# misc.net
KiCad netlist of a schematic drawn in Altium Designer
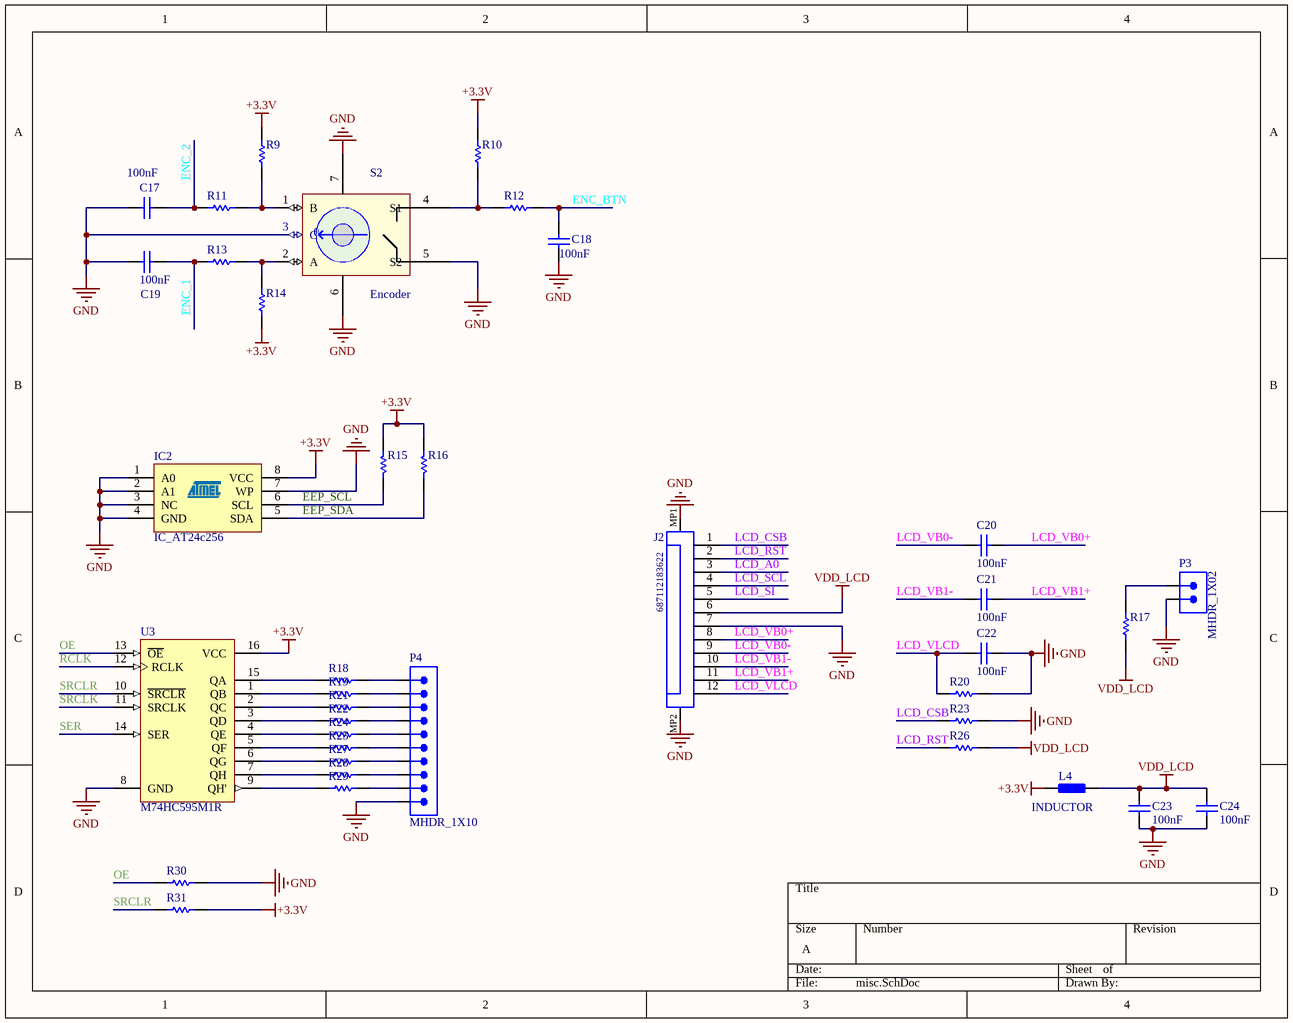
[diagram p0: misc.SchDoc]

(export (version "E")
  (design (tool "Eeschema 10.0.6"))
  (components
    (comp (ref "C17")
      (value "100nF")
      (footprint "CAPC3216M (1206)")
      (description "Bipolar Capacitor")
      (fields
        (field (name "VOLTAGE") "100V")
        (field (name "DESIGNER") "Eng. Saeid Jorablo")
        (field (name "PUBLISHER") "SJ Unlimited")
      )
      (libsource (lib "SJ Passive Components") (part "CAP_Bipolar"))
    )
    (comp (ref "C18")
      (value "100nF")
      (footprint "CAPC3216M (1206)")
      (description "Bipolar Capacitor")
      (fields
        (field (name "VOLTAGE") "100V")
        (field (name "DESIGNER") "Eng. Saeid Jorablo")
        (field (name "PUBLISHER") "SJ Unlimited")
      )
      (libsource (lib "SJ Passive Components") (part "CAP_Bipolar"))
    )
    (comp (ref "C19")
      (value "100nF")
      (footprint "CAPC3216M (1206)")
      (description "Bipolar Capacitor")
      (fields
        (field (name "VOLTAGE") "100V")
        (field (name "DESIGNER") "Eng. Saeid Jorablo")
        (field (name "PUBLISHER") "SJ Unlimited")
      )
      (libsource (lib "SJ Passive Components") (part "CAP_Bipolar"))
    )
    (comp (ref "C20")
      (value "100nF")
      (footprint "CAPC3216M (1206)")
      (description "Bipolar Capacitor")
      (fields
        (field (name "VOLTAGE") "100V")
        (field (name "DESIGNER") "Eng. Saeid Jorablo")
        (field (name "PUBLISHER") "SJ Unlimited")
      )
      (libsource (lib "SJ Passive Components") (part "CAP_Bipolar"))
    )
    (comp (ref "C21")
      (value "100nF")
      (footprint "CAPC3216M (1206)")
      (description "Bipolar Capacitor")
      (fields
        (field (name "VOLTAGE") "100V")
        (field (name "DESIGNER") "Eng. Saeid Jorablo")
        (field (name "PUBLISHER") "SJ Unlimited")
      )
      (libsource (lib "SJ Passive Components") (part "CAP_Bipolar"))
    )
    (comp (ref "C22")
      (value "100nF")
      (footprint "CAPC3216M (1206)")
      (description "Bipolar Capacitor")
      (fields
        (field (name "VOLTAGE") "100V")
        (field (name "DESIGNER") "Eng. Saeid Jorablo")
        (field (name "PUBLISHER") "SJ Unlimited")
      )
      (libsource (lib "SJ Passive Components") (part "CAP_Bipolar"))
    )
    (comp (ref "C23")
      (value "100nF")
      (footprint "CAPC3216M (1206)")
      (description "Bipolar Capacitor")
      (fields
        (field (name "VOLTAGE") "100V")
        (field (name "DESIGNER") "Eng. Saeid Jorablo")
        (field (name "PUBLISHER") "SJ Unlimited")
      )
      (libsource (lib "SJ Passive Components") (part "CAP_Bipolar"))
    )
    (comp (ref "C24")
      (value "100nF")
      (footprint "CAPC3216M (1206)")
      (description "Bipolar Capacitor")
      (fields
        (field (name "VOLTAGE") "100V")
        (field (name "DESIGNER") "Eng. Saeid Jorablo")
        (field (name "PUBLISHER") "SJ Unlimited")
      )
      (libsource (lib "SJ Passive Components") (part "CAP_Bipolar"))
    )
    (comp (ref "IC2")
      (value "IC_AT24c256")
      (footprint "CDIP8")
      (description "EEPROM Memory")
      (fields (field (name "DESIGNER") "Eng. Saeid Jorablo"))
      (libsource (lib "SJ Altium Library") (part "IC_AT24c256"))
    )
    (comp (ref "J2")
      (value "687112183622")
      (footprint "PCBComponent_1")
      (description "SMT ZIF Connectors Low Profile WR-FPC, Horizontal, Top Contact, pitch 0.6 mm, 12 pins")
      (fields (field (name "PUBLISHER") "Wurth Elektronik"))
      (libsource (lib "Altium_FPC_CONNECTORS (rev18c)") (part "687112183622"))
    )
    (comp (ref "L4")
      (value "INDUCTOR")
      (footprint "INDC4532")
      (description "Inductor")
      (fields (field (name "PUBLISHER") "SJ Unlimited") (field (name "DESIGNER") "Eng. Saeid Jorablo"))
      (libsource (lib "SJ Passive Components") (part "INDUCTOR"))
    )
    (comp (ref "P3")
      (value "MHDR_1X02")
      (footprint "MHDR1X02-254P")
      (description "Male Header 1X02")
      (libsource (lib "SJ Sockets & Connectors") (part "MHDR_1X02"))
    )
    (comp (ref "P4")
      (value "MHDR_1X10")
      (footprint "MHDR1X10-254P - E")
      (description "Male Header 1X10")
      (libsource (lib "SJ Sockets & Connectors") (part "MHDR_1X10"))
    )
    (comp (ref "R9")
      (value "1K")
      (footprint "RESC3216X60M (1206)")
      (description "Resistor")
      (fields
        (field (name "TOLERANCE") "5%")
        (field (name "POWER") "1/8 W")
        (field (name "DESIGNER") "Eng. Saeid Jorablo")
        (field (name "PUBLISHER") "SJ Unlimited")
      )
      (libsource (lib "SJ Passive Components") (part "RES"))
    )
    (comp (ref "R10")
      (value "1K")
      (footprint "RESC3216X60M (1206)")
      (description "Resistor")
      (fields
        (field (name "TOLERANCE") "5%")
        (field (name "POWER") "1/8 W")
        (field (name "DESIGNER") "Eng. Saeid Jorablo")
        (field (name "PUBLISHER") "SJ Unlimited")
      )
      (libsource (lib "SJ Passive Components") (part "RES"))
    )
    (comp (ref "R11")
      (value "1K")
      (footprint "RESC3216X60M (1206)")
      (description "Resistor")
      (fields
        (field (name "TOLERANCE") "5%")
        (field (name "POWER") "1/8 W")
        (field (name "DESIGNER") "Eng. Saeid Jorablo")
        (field (name "PUBLISHER") "SJ Unlimited")
      )
      (libsource (lib "SJ Passive Components") (part "RES"))
    )
    (comp (ref "R12")
      (value "1K")
      (footprint "RESC3216X60M (1206)")
      (description "Resistor")
      (fields
        (field (name "TOLERANCE") "5%")
        (field (name "POWER") "1/8 W")
        (field (name "DESIGNER") "Eng. Saeid Jorablo")
        (field (name "PUBLISHER") "SJ Unlimited")
      )
      (libsource (lib "SJ Passive Components") (part "RES"))
    )
    (comp (ref "R13")
      (value "1K")
      (footprint "RESC3216X60M (1206)")
      (description "Resistor")
      (fields
        (field (name "TOLERANCE") "5%")
        (field (name "POWER") "1/8 W")
        (field (name "DESIGNER") "Eng. Saeid Jorablo")
        (field (name "PUBLISHER") "SJ Unlimited")
      )
      (libsource (lib "SJ Passive Components") (part "RES"))
    )
    (comp (ref "R14")
      (value "1K")
      (footprint "RESC3216X60M (1206)")
      (description "Resistor")
      (fields
        (field (name "TOLERANCE") "5%")
        (field (name "POWER") "1/8 W")
        (field (name "DESIGNER") "Eng. Saeid Jorablo")
        (field (name "PUBLISHER") "SJ Unlimited")
      )
      (libsource (lib "SJ Passive Components") (part "RES"))
    )
    (comp (ref "R15")
      (value "1K")
      (footprint "RESC3216X60M (1206)")
      (description "Resistor")
      (fields
        (field (name "TOLERANCE") "5%")
        (field (name "POWER") "1/8 W")
        (field (name "DESIGNER") "Eng. Saeid Jorablo")
        (field (name "PUBLISHER") "SJ Unlimited")
      )
      (libsource (lib "SJ Passive Components") (part "RES"))
    )
    (comp (ref "R16")
      (value "1K")
      (footprint "RESC3216X60M (1206)")
      (description "Resistor")
      (fields
        (field (name "TOLERANCE") "5%")
        (field (name "POWER") "1/8 W")
        (field (name "DESIGNER") "Eng. Saeid Jorablo")
        (field (name "PUBLISHER") "SJ Unlimited")
      )
      (libsource (lib "SJ Passive Components") (part "RES"))
    )
    (comp (ref "R17")
      (value "1K")
      (footprint "RESC3216X60M (1206)")
      (description "Resistor")
      (fields
        (field (name "TOLERANCE") "5%")
        (field (name "POWER") "1/8 W")
        (field (name "DESIGNER") "Eng. Saeid Jorablo")
        (field (name "PUBLISHER") "SJ Unlimited")
      )
      (libsource (lib "SJ Passive Components") (part "RES"))
    )
    (comp (ref "R18")
      (value "1K")
      (footprint "RESC3216X60M (1206)")
      (description "Resistor")
      (fields
        (field (name "TOLERANCE") "5%")
        (field (name "POWER") "1/8 W")
        (field (name "DESIGNER") "Eng. Saeid Jorablo")
        (field (name "PUBLISHER") "SJ Unlimited")
      )
      (libsource (lib "SJ Passive Components") (part "RES"))
    )
    (comp (ref "R19")
      (value "1K")
      (footprint "RESC3216X60M (1206)")
      (description "Resistor")
      (fields
        (field (name "TOLERANCE") "5%")
        (field (name "POWER") "1/8 W")
        (field (name "DESIGNER") "Eng. Saeid Jorablo")
        (field (name "PUBLISHER") "SJ Unlimited")
      )
      (libsource (lib "SJ Passive Components") (part "RES"))
    )
    (comp (ref "R20")
      (value "1K")
      (footprint "RESC3216X60M (1206)")
      (description "Resistor")
      (fields
        (field (name "TOLERANCE") "5%")
        (field (name "POWER") "1/8 W")
        (field (name "DESIGNER") "Eng. Saeid Jorablo")
        (field (name "PUBLISHER") "SJ Unlimited")
      )
      (libsource (lib "SJ Passive Components") (part "RES"))
    )
    (comp (ref "R21")
      (value "1K")
      (footprint "RESC3216X60M (1206)")
      (description "Resistor")
      (fields
        (field (name "TOLERANCE") "5%")
        (field (name "POWER") "1/8 W")
        (field (name "DESIGNER") "Eng. Saeid Jorablo")
        (field (name "PUBLISHER") "SJ Unlimited")
      )
      (libsource (lib "SJ Passive Components") (part "RES"))
    )
    (comp (ref "R22")
      (value "1K")
      (footprint "RESC3216X60M (1206)")
      (description "Resistor")
      (fields
        (field (name "TOLERANCE") "5%")
        (field (name "POWER") "1/8 W")
        (field (name "DESIGNER") "Eng. Saeid Jorablo")
        (field (name "PUBLISHER") "SJ Unlimited")
      )
      (libsource (lib "SJ Passive Components") (part "RES"))
    )
    (comp (ref "R23")
      (value "1K")
      (footprint "RESC3216X60M (1206)")
      (description "Resistor")
      (fields
        (field (name "TOLERANCE") "5%")
        (field (name "POWER") "1/8 W")
        (field (name "DESIGNER") "Eng. Saeid Jorablo")
        (field (name "PUBLISHER") "SJ Unlimited")
      )
      (libsource (lib "SJ Passive Components") (part "RES"))
    )
    (comp (ref "R24")
      (value "1K")
      (footprint "RESC3216X60M (1206)")
      (description "Resistor")
      (fields
        (field (name "TOLERANCE") "5%")
        (field (name "POWER") "1/8 W")
        (field (name "DESIGNER") "Eng. Saeid Jorablo")
        (field (name "PUBLISHER") "SJ Unlimited")
      )
      (libsource (lib "SJ Passive Components") (part "RES"))
    )
    (comp (ref "R25")
      (value "1K")
      (footprint "RESC3216X60M (1206)")
      (description "Resistor")
      (fields
        (field (name "TOLERANCE") "5%")
        (field (name "POWER") "1/8 W")
        (field (name "DESIGNER") "Eng. Saeid Jorablo")
        (field (name "PUBLISHER") "SJ Unlimited")
      )
      (libsource (lib "SJ Passive Components") (part "RES"))
    )
    (comp (ref "R26")
      (value "1K")
      (footprint "RESC3216X60M (1206)")
      (description "Resistor")
      (fields
        (field (name "TOLERANCE") "5%")
        (field (name "POWER") "1/8 W")
        (field (name "DESIGNER") "Eng. Saeid Jorablo")
        (field (name "PUBLISHER") "SJ Unlimited")
      )
      (libsource (lib "SJ Passive Components") (part "RES"))
    )
    (comp (ref "R27")
      (value "1K")
      (footprint "RESC3216X60M (1206)")
      (description "Resistor")
      (fields
        (field (name "TOLERANCE") "5%")
        (field (name "POWER") "1/8 W")
        (field (name "DESIGNER") "Eng. Saeid Jorablo")
        (field (name "PUBLISHER") "SJ Unlimited")
      )
      (libsource (lib "SJ Passive Components") (part "RES"))
    )
    (comp (ref "R28")
      (value "1K")
      (footprint "RESC3216X60M (1206)")
      (description "Resistor")
      (fields
        (field (name "TOLERANCE") "5%")
        (field (name "POWER") "1/8 W")
        (field (name "DESIGNER") "Eng. Saeid Jorablo")
        (field (name "PUBLISHER") "SJ Unlimited")
      )
      (libsource (lib "SJ Passive Components") (part "RES"))
    )
    (comp (ref "R29")
      (value "1K")
      (footprint "RESC3216X60M (1206)")
      (description "Resistor")
      (fields
        (field (name "TOLERANCE") "5%")
        (field (name "POWER") "1/8 W")
        (field (name "DESIGNER") "Eng. Saeid Jorablo")
        (field (name "PUBLISHER") "SJ Unlimited")
      )
      (libsource (lib "SJ Passive Components") (part "RES"))
    )
    (comp (ref "R30")
      (value "1K")
      (footprint "RESC3216X60M (1206)")
      (description "Resistor")
      (fields
        (field (name "TOLERANCE") "5%")
        (field (name "POWER") "1/8 W")
        (field (name "DESIGNER") "Eng. Saeid Jorablo")
        (field (name "PUBLISHER") "SJ Unlimited")
      )
      (libsource (lib "SJ Passive Components") (part "RES"))
    )
    (comp (ref "R31")
      (value "1K")
      (footprint "RESC3216X60M (1206)")
      (description "Resistor")
      (fields
        (field (name "TOLERANCE") "5%")
        (field (name "POWER") "1/8 W")
        (field (name "DESIGNER") "Eng. Saeid Jorablo")
        (field (name "PUBLISHER") "SJ Unlimited")
      )
      (libsource (lib "SJ Passive Components") (part "RES"))
    )
    (comp (ref "S2") (value "Encoder") (footprint "Encoder") (libsource (lib "stm8") (part "Encoder")))
    (comp (ref "U3")
      (value "M74HC595M1R")
      (footprint "SO16_L")
      (description "8 Bit Shift Register with Output Latches (3 STATE)")
      (fields (field (name "PUBLISHER") "Altium Limited"))
      (libsource (lib "ST Logic Register") (part "M74HC595M1R"))
    )
  )
  (nets
    (net (code "1") (name "+3.3V") (class "Default")
      (node (ref "IC2") (pin "8") (pinfunction "VCC_8") (pintype "power_in"))
      (node (ref "L4") (pin "1") (pinfunction "1_1") (pintype "passive"))
      (node (ref "R10") (pin "2") (pinfunction "2_2") (pintype "passive"))
      (node (ref "R14") (pin "1") (pinfunction "1_1") (pintype "passive"))
      (node (ref "R15") (pin "1") (pinfunction "1_1") (pintype "passive"))
      (node (ref "R16") (pin "1") (pinfunction "1_1") (pintype "passive"))
      (node (ref "R31") (pin "1") (pinfunction "1_1") (pintype "passive"))
      (node (ref "R9") (pin "2") (pinfunction "2_2") (pintype "passive"))
      (node (ref "U3") (pin "16") (pinfunction "VCC_16") (pintype "power_in"))
    )
    (net (code "2") (name "/EEP_SCL") (class "Default")
      (node (ref "IC2") (pin "6") (pinfunction "SCL_6") (pintype "passive"))
      (node (ref "R15") (pin "2") (pinfunction "2_2") (pintype "passive"))
    )
    (net (code "3") (name "/EEP_SDA") (class "Default")
      (node (ref "IC2") (pin "5") (pinfunction "SDA_5") (pintype "passive"))
      (node (ref "R16") (pin "2") (pinfunction "2_2") (pintype "passive"))
    )
    (net (code "4") (name "/ENC_1") (class "Default")
      (node (ref "C19") (pin "2") (pinfunction "-_2") (pintype "passive"))
      (node (ref "R13") (pin "2") (pinfunction "2_2") (pintype "passive"))
    )
    (net (code "5") (name "/ENC_2") (class "Default")
      (node (ref "C17") (pin "2") (pinfunction "-_2") (pintype "passive"))
      (node (ref "R11") (pin "2") (pinfunction "2_2") (pintype "passive"))
    )
    (net (code "6") (name "/ENC_BTN") (class "Default")
      (node (ref "C18") (pin "1") (pinfunction "+_1") (pintype "passive"))
      (node (ref "R12") (pin "1") (pinfunction "1_1") (pintype "passive"))
    )
    (net (code "7") (name "/LCD_A0") (class "Default")
      (node (ref "J2") (pin "3") (pinfunction "3_3") (pintype "passive"))
    )
    (net (code "8") (name "/LCD_CSB") (class "Default")
      (node (ref "J2") (pin "1") (pinfunction "1_1") (pintype "passive"))
      (node (ref "R23") (pin "2") (pinfunction "2_2") (pintype "passive"))
    )
    (net (code "9") (name "/LCD_RST") (class "Default")
      (node (ref "J2") (pin "2") (pinfunction "2_2") (pintype "passive"))
      (node (ref "R26") (pin "2") (pinfunction "2_2") (pintype "passive"))
    )
    (net (code "10") (name "/LCD_SCL") (class "Default")
      (node (ref "J2") (pin "4") (pinfunction "4_4") (pintype "passive"))
    )
    (net (code "11") (name "/LCD_SI") (class "Default")
      (node (ref "J2") (pin "5") (pinfunction "5_5") (pintype "passive"))
    )
    (net (code "12") (name "/LCD_VB0+") (class "Default")
      (node (ref "C20") (pin "1") (pinfunction "+_1") (pintype "passive"))
      (node (ref "J2") (pin "8") (pinfunction "8_8") (pintype "passive"))
    )
    (net (code "13") (name "/LCD_VB0-") (class "Default")
      (node (ref "C20") (pin "2") (pinfunction "-_2") (pintype "passive"))
      (node (ref "J2") (pin "9") (pinfunction "9_9") (pintype "passive"))
    )
    (net (code "14") (name "/LCD_VB1+") (class "Default")
      (node (ref "C21") (pin "1") (pinfunction "+_1") (pintype "passive"))
      (node (ref "J2") (pin "11") (pinfunction "11_11") (pintype "passive"))
    )
    (net (code "15") (name "/LCD_VB1-") (class "Default")
      (node (ref "C21") (pin "2") (pinfunction "-_2") (pintype "passive"))
      (node (ref "J2") (pin "10") (pinfunction "10_10") (pintype "passive"))
    )
    (net (code "16") (name "/LCD_VLCD") (class "Default")
      (node (ref "C22") (pin "1") (pinfunction "+_1") (pintype "passive"))
      (node (ref "J2") (pin "12") (pinfunction "12_12") (pintype "passive"))
      (node (ref "R20") (pin "2") (pinfunction "2_2") (pintype "passive"))
    )
    (net (code "17") (name "/OE") (class "Default")
      (node (ref "R30") (pin "2") (pinfunction "2_2") (pintype "passive"))
      (node (ref "U3") (pin "13") (pinfunction "~{OE}_13") (pintype "input"))
    )
    (net (code "18") (name "/RCLK") (class "Default")
      (node (ref "U3") (pin "12") (pinfunction "RCLK_12") (pintype "input"))
    )
    (net (code "19") (name "/SER") (class "Default")
      (node (ref "U3") (pin "14") (pinfunction "SER_14") (pintype "input"))
    )
    (net (code "20") (name "/SRCLK") (class "Default")
      (node (ref "U3") (pin "11") (pinfunction "SRCLK_11") (pintype "input"))
    )
    (net (code "21") (name "/SRCLR") (class "Default")
      (node (ref "R31") (pin "2") (pinfunction "2_2") (pintype "passive"))
      (node (ref "U3") (pin "10") (pinfunction "~{SRCLR}_10") (pintype "input"))
    )
    (net (code "22") (name "GND") (class "Default")
      (node (ref "C17") (pin "1") (pinfunction "+_1") (pintype "passive"))
      (node (ref "C18") (pin "2") (pinfunction "-_2") (pintype "passive"))
      (node (ref "C19") (pin "1") (pinfunction "+_1") (pintype "passive"))
      (node (ref "C22") (pin "2") (pinfunction "-_2") (pintype "passive"))
      (node (ref "C23") (pin "2") (pinfunction "-_2") (pintype "passive"))
      (node (ref "C24") (pin "2") (pinfunction "-_2") (pintype "passive"))
      (node (ref "IC2") (pin "1") (pinfunction "A0_1") (pintype "passive"))
      (node (ref "IC2") (pin "2") (pinfunction "A1_2") (pintype "passive"))
      (node (ref "IC2") (pin "3") (pinfunction "NC_3") (pintype "passive"))
      (node (ref "IC2") (pin "4") (pinfunction "GND_4") (pintype "power_in"))
      (node (ref "IC2") (pin "7") (pinfunction "WP_7") (pintype "passive"))
      (node (ref "J2") (pin "7") (pinfunction "7_7") (pintype "passive"))
      (node (ref "J2") (pin "MP1") (pinfunction "MP1_MP1") (pintype "passive"))
      (node (ref "J2") (pin "MP2") (pinfunction "MP2_MP2") (pintype "passive"))
      (node (ref "P3") (pin "2") (pinfunction "2_2") (pintype "passive"))
      (node (ref "P4") (pin "10") (pinfunction "10_10") (pintype "passive"))
      (node (ref "R20") (pin "1") (pinfunction "1_1") (pintype "passive"))
      (node (ref "R23") (pin "1") (pinfunction "1_1") (pintype "passive"))
      (node (ref "R30") (pin "1") (pinfunction "1_1") (pintype "passive"))
      (node (ref "S2") (pin "3") (pinfunction "C_3") (pintype "bidirectional"))
      (node (ref "S2") (pin "5") (pinfunction "S2_5") (pintype "passive"))
      (node (ref "S2") (pin "6") (pinfunction "CHASIS_6") (pintype "passive"))
      (node (ref "S2") (pin "7") (pinfunction "CHASIS_7") (pintype "passive"))
      (node (ref "U3") (pin "8") (pinfunction "GND_8") (pintype "power_in"))
    )
    (net (code "23") (name "Net-(P3-Pad1)") (class "Default")
      (node (ref "P3") (pin "1") (pinfunction "1_1") (pintype "passive"))
      (node (ref "R17") (pin "1") (pinfunction "1_1") (pintype "passive"))
    )
    (net (code "24") (name "Net-(P4-Pad1)") (class "Default")
      (node (ref "P4") (pin "1") (pinfunction "1_1") (pintype "passive"))
      (node (ref "R18") (pin "1") (pinfunction "1_1") (pintype "passive"))
    )
    (net (code "25") (name "Net-(P4-Pad2)") (class "Default")
      (node (ref "P4") (pin "2") (pinfunction "2_2") (pintype "passive"))
      (node (ref "R19") (pin "1") (pinfunction "1_1") (pintype "passive"))
    )
    (net (code "26") (name "Net-(P4-Pad3)") (class "Default")
      (node (ref "P4") (pin "3") (pinfunction "3_3") (pintype "passive"))
      (node (ref "R21") (pin "1") (pinfunction "1_1") (pintype "passive"))
    )
    (net (code "27") (name "Net-(P4-Pad4)") (class "Default")
      (node (ref "P4") (pin "4") (pinfunction "4_4") (pintype "passive"))
      (node (ref "R22") (pin "1") (pinfunction "1_1") (pintype "passive"))
    )
    (net (code "28") (name "Net-(P4-Pad5)") (class "Default")
      (node (ref "P4") (pin "5") (pinfunction "5_5") (pintype "passive"))
      (node (ref "R24") (pin "1") (pinfunction "1_1") (pintype "passive"))
    )
    (net (code "29") (name "Net-(P4-Pad6)") (class "Default")
      (node (ref "P4") (pin "6") (pinfunction "6_6") (pintype "passive"))
      (node (ref "R25") (pin "1") (pinfunction "1_1") (pintype "passive"))
    )
    (net (code "30") (name "Net-(P4-Pad7)") (class "Default")
      (node (ref "P4") (pin "7") (pinfunction "7_7") (pintype "passive"))
      (node (ref "R27") (pin "1") (pinfunction "1_1") (pintype "passive"))
    )
    (net (code "31") (name "Net-(P4-Pad8)") (class "Default")
      (node (ref "P4") (pin "8") (pinfunction "8_8") (pintype "passive"))
      (node (ref "R28") (pin "1") (pinfunction "1_1") (pintype "passive"))
    )
    (net (code "32") (name "Net-(P4-Pad9)") (class "Default")
      (node (ref "P4") (pin "9") (pinfunction "9_9") (pintype "passive"))
      (node (ref "R29") (pin "1") (pinfunction "1_1") (pintype "passive"))
    )
    (net (code "33") (name "Net-(S2-A)") (class "Default")
      (node (ref "R13") (pin "1") (pinfunction "1_1") (pintype "passive"))
      (node (ref "R14") (pin "2") (pinfunction "2_2") (pintype "passive"))
      (node (ref "S2") (pin "2") (pinfunction "A_2") (pintype "bidirectional"))
    )
    (net (code "34") (name "Net-(S2-B)") (class "Default")
      (node (ref "R11") (pin "1") (pinfunction "1_1") (pintype "passive"))
      (node (ref "R9") (pin "1") (pinfunction "1_1") (pintype "passive"))
      (node (ref "S2") (pin "1") (pinfunction "B_1") (pintype "bidirectional"))
    )
    (net (code "35") (name "Net-(S2-S1)") (class "Default")
      (node (ref "R10") (pin "1") (pinfunction "1_1") (pintype "passive"))
      (node (ref "R12") (pin "2") (pinfunction "2_2") (pintype "passive"))
      (node (ref "S2") (pin "4") (pinfunction "S1_4") (pintype "passive"))
    )
    (net (code "36") (name "Net-(U3-QA)") (class "Default")
      (node (ref "R18") (pin "2") (pinfunction "2_2") (pintype "passive"))
      (node (ref "U3") (pin "15") (pinfunction "QA_15") (pintype "tri_state"))
    )
    (net (code "37") (name "Net-(U3-QB)") (class "Default")
      (node (ref "R19") (pin "2") (pinfunction "2_2") (pintype "passive"))
      (node (ref "U3") (pin "1") (pinfunction "QB_1") (pintype "tri_state"))
    )
    (net (code "38") (name "Net-(U3-QC)") (class "Default")
      (node (ref "R21") (pin "2") (pinfunction "2_2") (pintype "passive"))
      (node (ref "U3") (pin "2") (pinfunction "QC_2") (pintype "tri_state"))
    )
    (net (code "39") (name "Net-(U3-QD)") (class "Default")
      (node (ref "R22") (pin "2") (pinfunction "2_2") (pintype "passive"))
      (node (ref "U3") (pin "3") (pinfunction "QD_3") (pintype "tri_state"))
    )
    (net (code "40") (name "Net-(U3-QE)") (class "Default")
      (node (ref "R24") (pin "2") (pinfunction "2_2") (pintype "passive"))
      (node (ref "U3") (pin "4") (pinfunction "QE_4") (pintype "tri_state"))
    )
    (net (code "41") (name "Net-(U3-QF)") (class "Default")
      (node (ref "R25") (pin "2") (pinfunction "2_2") (pintype "passive"))
      (node (ref "U3") (pin "5") (pinfunction "QF_5") (pintype "tri_state"))
    )
    (net (code "42") (name "Net-(U3-QG)") (class "Default")
      (node (ref "R27") (pin "2") (pinfunction "2_2") (pintype "passive"))
      (node (ref "U3") (pin "6") (pinfunction "QG_6") (pintype "tri_state"))
    )
    (net (code "43") (name "Net-(U3-QH')") (class "Default")
      (node (ref "R29") (pin "2") (pinfunction "2_2") (pintype "passive"))
      (node (ref "U3") (pin "9") (pinfunction "QH'_9") (pintype "output"))
    )
    (net (code "44") (name "Net-(U3-QH)") (class "Default")
      (node (ref "R28") (pin "2") (pinfunction "2_2") (pintype "passive"))
      (node (ref "U3") (pin "7") (pinfunction "QH_7") (pintype "tri_state"))
    )
    (net (code "45") (name "VDD_LCD") (class "Default")
      (node (ref "C23") (pin "1") (pinfunction "+_1") (pintype "passive"))
      (node (ref "C24") (pin "1") (pinfunction "+_1") (pintype "passive"))
      (node (ref "J2") (pin "6") (pinfunction "6_6") (pintype "passive"))
      (node (ref "L4") (pin "2") (pinfunction "2_2") (pintype "passive"))
      (node (ref "R17") (pin "2") (pinfunction "2_2") (pintype "passive"))
      (node (ref "R26") (pin "1") (pinfunction "1_1") (pintype "passive"))
    )
  )
)
